# FEEL_2021_actuator.net
KiCad netlist of a schematic drawn in Altium Designer
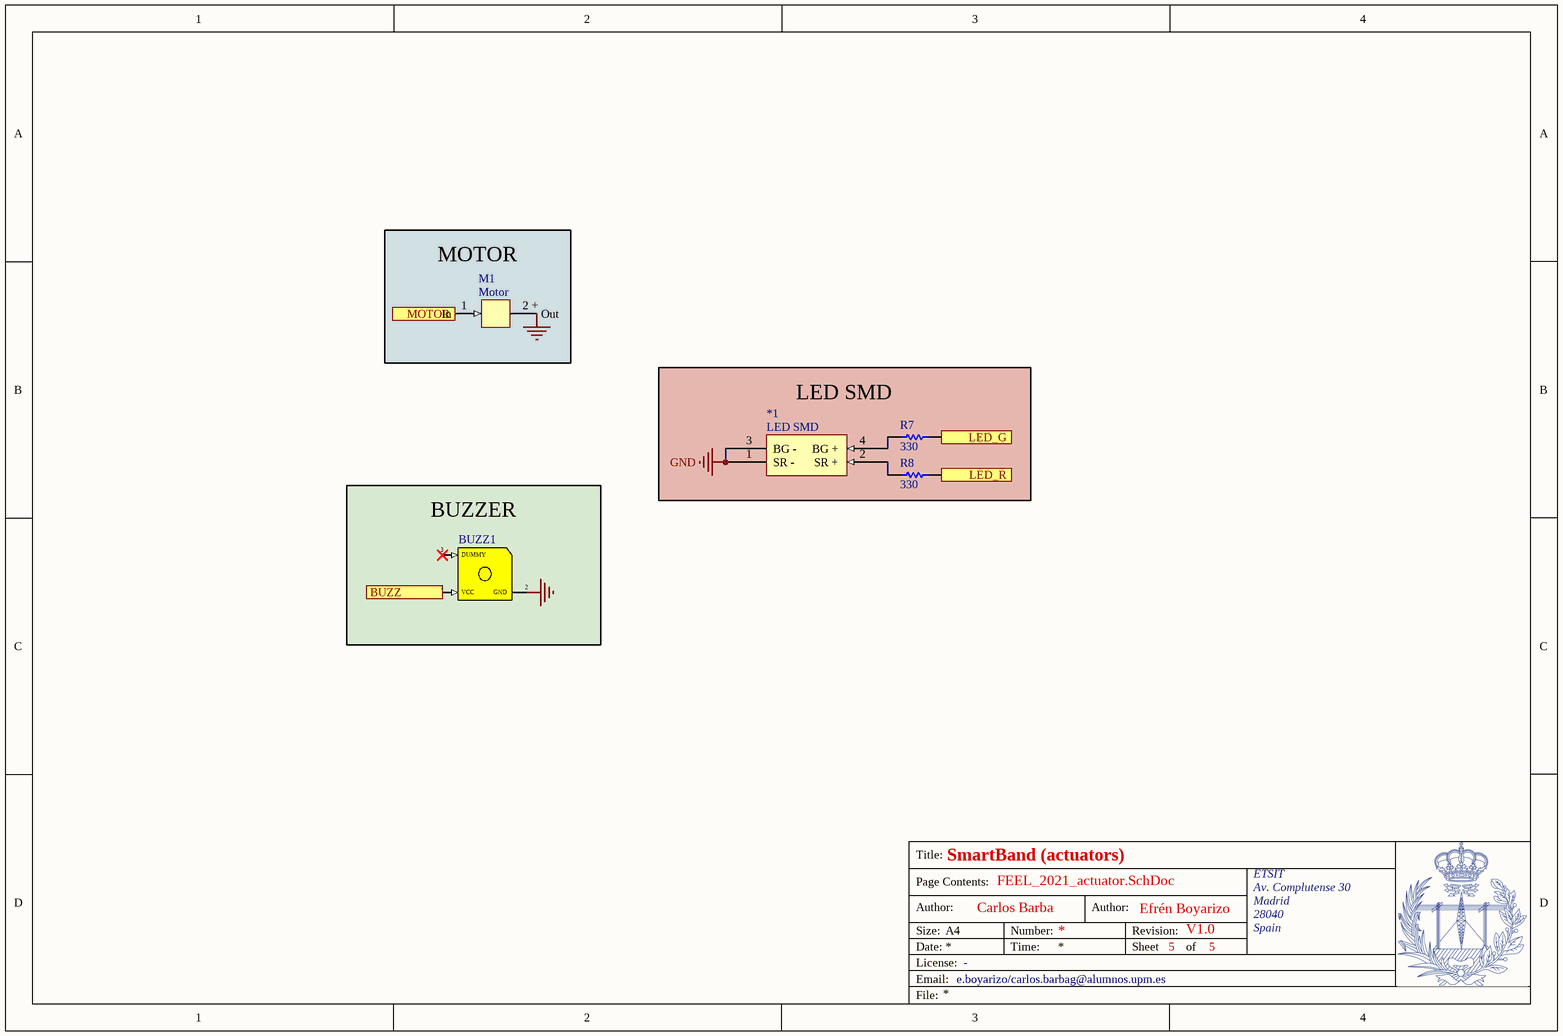
[diagram p0: FEEL_2021_actuator.SchDoc]

(export (version "E")
  (design (tool "Eeschema 10.0.6"))
  (components
    (comp (ref "*1") (value "LED") (footprint "LED_SMD") (libsource (lib "FEEL2122") (part "LED")))
    (comp (ref "BUZZ1")
      (value "Surface_Mount_Buzzer")
      (footprint "buzzer")
      (libsource (lib "FEEL2122") (part "Surface_Mount_Buzzer"))
    )
    (comp (ref "M1") (value "MOTOR") (footprint "Motor") (libsource (lib "FEEL2122") (part "MOTOR")))
    (comp (ref "R7")
      (value "330")
      (footprint "RESC1609X50X30NL8T20")
      (description "Chip Resistor, 0 Ohm, Jumper, 100 mW, -55 to 155 degC, 0603 (1608 Metric), RoHS, Tape and Reel")
      (fields (field (name "MANUFACTURER") "Vishay Semiconductor"))
      (libsource (lib "Altium Content Vault") (part "RES-2"))
    )
    (comp (ref "R8")
      (value "330")
      (footprint "RESC1609X50X30NL8T20")
      (description "Chip Resistor, 0 Ohm, Jumper, 100 mW, -55 to 155 degC, 0603 (1608 Metric), RoHS, Tape and Reel")
      (fields (field (name "MANUFACTURER") "Vishay Semiconductor"))
      (libsource (lib "Altium Content Vault") (part "RES-2"))
    )
  )
  (nets
    (net (code "1") (name "/BUZZ") (class "Default")
      (node (ref "BUZZ1") (pin "1") (pinfunction "VCC_1") (pintype "input"))
    )
    (net (code "2") (name "/LED_G") (class "Default")
      (node (ref "R7") (pin "2") (pinfunction "2_2") (pintype "passive"))
    )
    (net (code "3") (name "/LED_R") (class "Default")
      (node (ref "R8") (pin "2") (pinfunction "2_2") (pintype "passive"))
    )
    (net (code "4") (name "/MOTOR") (class "Default")
      (node (ref "M1") (pin "1") (pinfunction "In_1") (pintype "input"))
    )
    (net (code "5") (name "GND") (class "Default")
      (node (ref "*1") (pin "1") (pinfunction "SR_-_1") (pintype "passive"))
      (node (ref "*1") (pin "3") (pinfunction "BG_-_3") (pintype "passive"))
      (node (ref "BUZZ1") (pin "2") (pinfunction "GND_2") (pintype "power_in"))
      (node (ref "M1") (pin "2_+") (pinfunction "Out_2_+") (pintype "passive"))
    )
    (net (code "6") (name "Net-(*1-BG_+)") (class "Default")
      (node (ref "*1") (pin "4") (pinfunction "BG_+_4") (pintype "input"))
      (node (ref "R7") (pin "1") (pinfunction "1_1") (pintype "passive"))
    )
    (net (code "7") (name "Net-(*1-SR_+)") (class "Default")
      (node (ref "*1") (pin "2") (pinfunction "SR_+_2") (pintype "input"))
      (node (ref "R8") (pin "1") (pinfunction "1_1") (pintype "passive"))
    )
    (net (code "8") (name "unconnected-(BUZZ1-DUMMY-Pad3)") (class "Default")
      (node (ref "BUZZ1") (pin "3") (pinfunction "DUMMY_3") (pintype "input+no_connect"))
    )
  )
)
